# Grove_-_Gas_Sensor_O2_v1_0.net
KiCad netlist of a schematic drawn in EAGLE
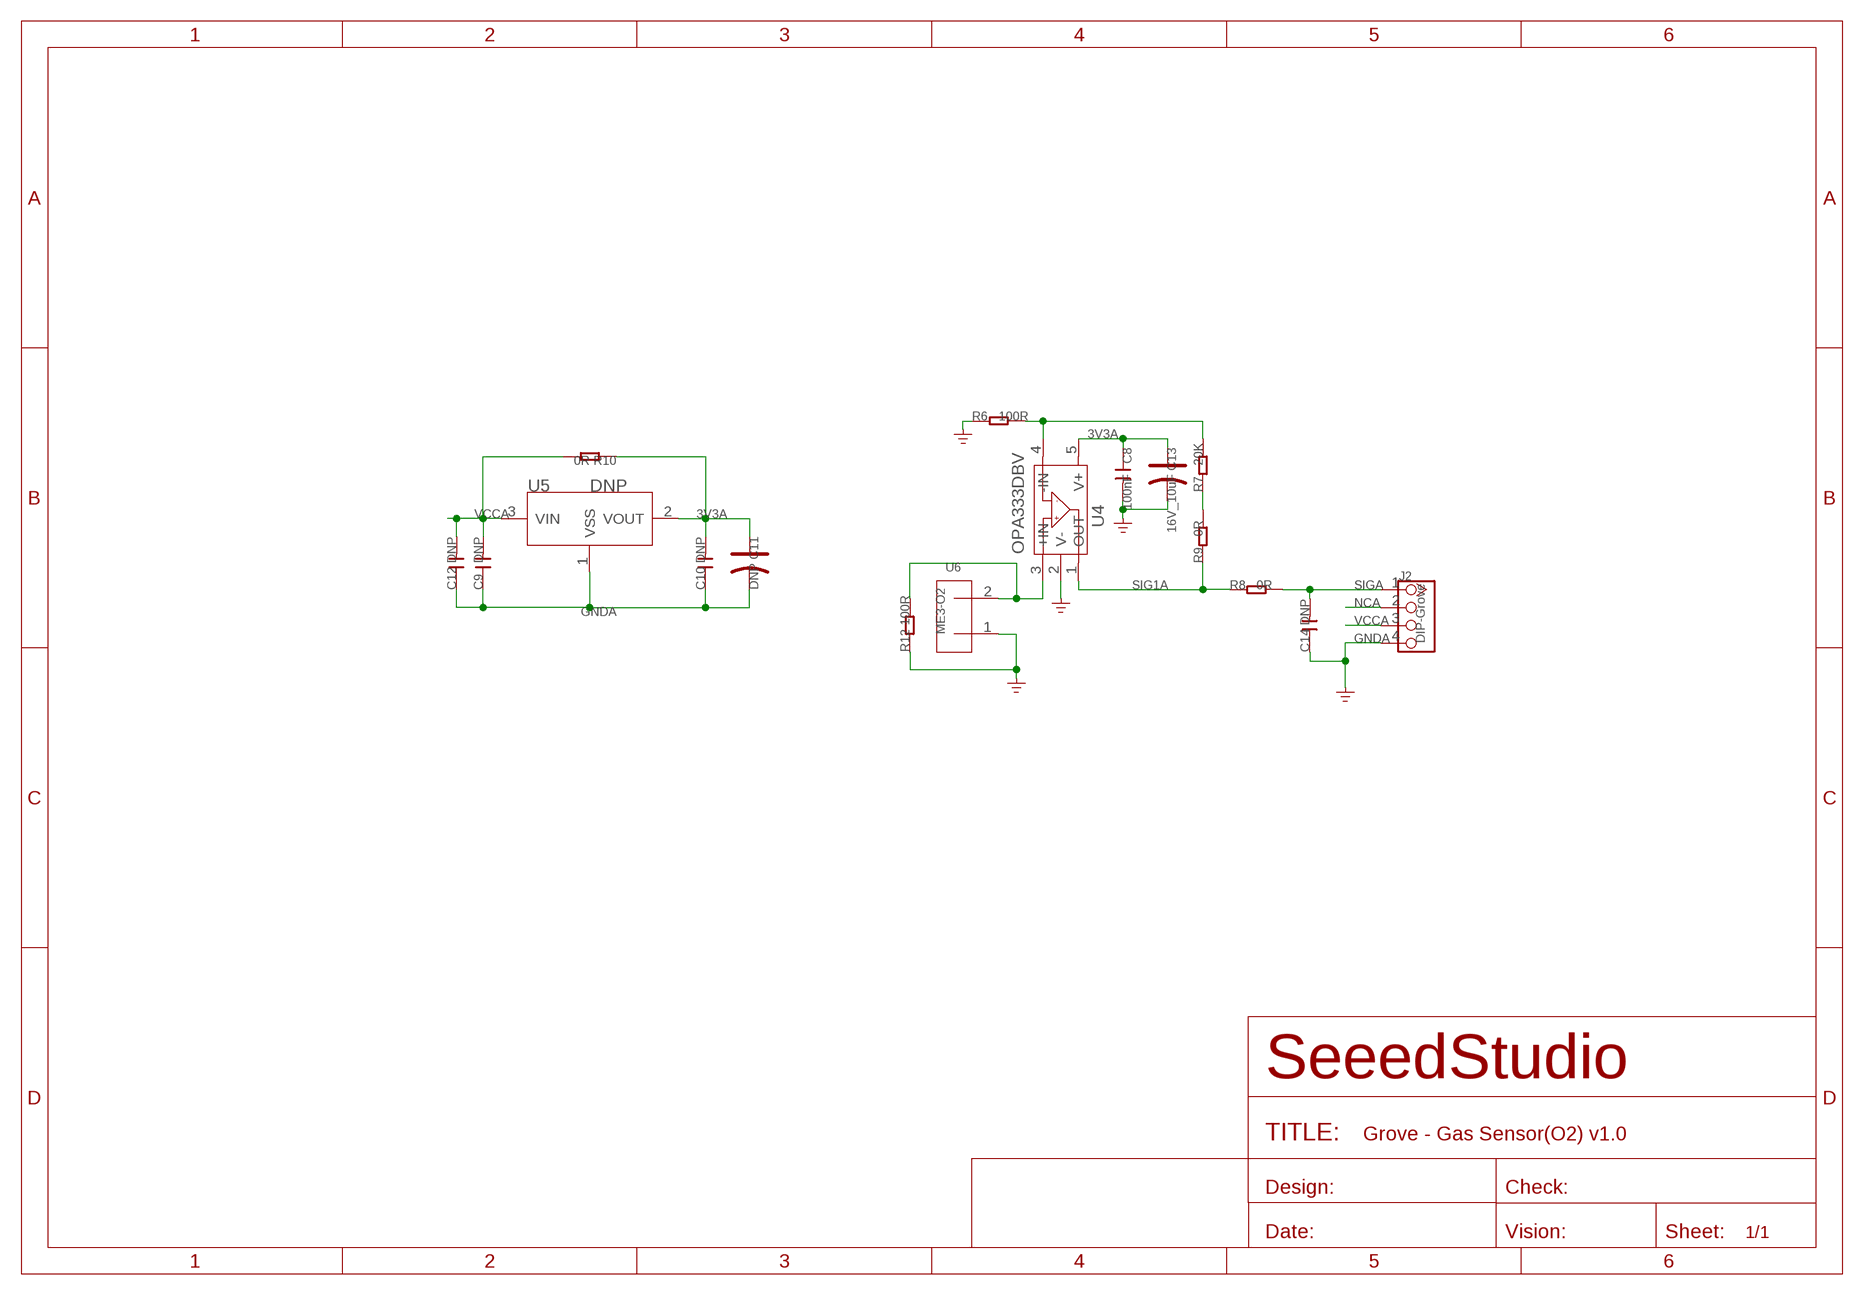
[diagram p0: schematic, sheet 1]

(export (version "E")
  (design (tool "Eeschema 10.0.6"))
  (components
    (comp (ref "C8")
      (value "100nF")
      (footprint "eagle-import:C0603")
      (libsource (lib "eagle-import") (part "C-0603"))
    )
    (comp (ref "C9")
      (value "DNP")
      (footprint "eagle-import:C0603")
      (libsource (lib "eagle-import") (part "C-0603"))
    )
    (comp (ref "C10")
      (value "DNP")
      (footprint "eagle-import:C0603")
      (libsource (lib "eagle-import") (part "C-0603"))
    )
    (comp (ref "C11")
      (value "DNP")
      (footprint "eagle-import:AVX-A")
      (libsource (lib "eagle-import") (part "CAP-AVX-A"))
    )
    (comp (ref "C12")
      (value "DNP")
      (footprint "eagle-import:C0805")
      (libsource (lib "eagle-import") (part "C-0805"))
    )
    (comp (ref "C13")
      (value "16V_10uF")
      (footprint "eagle-import:AVX-A")
      (libsource (lib "eagle-import") (part "CAP-AVX-A"))
    )
    (comp (ref "C14")
      (value "DNP")
      (footprint "eagle-import:C0805")
      (libsource (lib "eagle-import") (part "C-0805"))
    )
    (comp (ref "J2")
      (value "DIP-Grove")
      (footprint "eagle-import:4P-2.0")
      (libsource (lib "eagle-import") (part "TWIG-4P-2.0-2.0"))
    )
    (comp (ref "R6")
      (value "100R")
      (footprint "eagle-import:R0603")
      (libsource (lib "eagle-import") (part "R-0603"))
    )
    (comp (ref "R7")
      (value "20K")
      (footprint "eagle-import:R0603")
      (libsource (lib "eagle-import") (part "R-0603"))
    )
    (comp (ref "R8")
      (value "0R")
      (footprint "eagle-import:R0603")
      (libsource (lib "eagle-import") (part "R-0603"))
    )
    (comp (ref "R9")
      (value "0R")
      (footprint "eagle-import:R0603")
      (libsource (lib "eagle-import") (part "R-0603"))
    )
    (comp (ref "R10")
      (value "0R")
      (footprint "eagle-import:R0603")
      (libsource (lib "eagle-import") (part "R-0603"))
    )
    (comp (ref "R12")
      (value "100R")
      (footprint "eagle-import:R0603")
      (libsource (lib "eagle-import") (part "R-0603"))
    )
    (comp (ref "U4")
      (value "OPA333DBV")
      (footprint "eagle-import:SOT23-5")
      (libsource (lib "eagle-import") (part "OPA333DBV"))
    )
    (comp (ref "U5")
      (value "DNP")
      (footprint "eagle-import:SOT23")
      (libsource (lib "eagle-import") (part "XC6206MR"))
    )
    (comp (ref "U6")
      (value "ME3-O2")
      (footprint "eagle-import:2P-D20X16H")
      (libsource (lib "eagle-import") (part "ME3-O2"))
    )
  )
  (nets
    (net (code "1") (name "/3V3A") (class "Default")
      (node (ref "C10") (pin "2") (pinfunction "2_2") (pintype "passive"))
      (node (ref "C11") (pin "+") (pinfunction "+_+") (pintype "passive"))
      (node (ref "C13") (pin "+") (pinfunction "+_+") (pintype "passive"))
      (node (ref "C8") (pin "1") (pinfunction "1_1") (pintype "passive"))
      (node (ref "R10") (pin "1") (pinfunction "1_1") (pintype "passive"))
      (node (ref "U4") (pin "5") (pinfunction "V+_5") (pintype "bidirectional"))
      (node (ref "U5") (pin "2") (pinfunction "VOUT_2") (pintype "output"))
    )
    (net (code "2") (name "/NCA") (class "Default")
      (node (ref "J2") (pin "2") (pinfunction "2_2") (pintype "bidirectional"))
    )
    (net (code "3") (name "/SIG1A") (class "Default")
      (node (ref "R8") (pin "1") (pinfunction "1_1") (pintype "passive"))
      (node (ref "R9") (pin "1") (pinfunction "1_1") (pintype "passive"))
      (node (ref "U4") (pin "1") (pinfunction "OUT_1") (pintype "bidirectional"))
    )
    (net (code "4") (name "/SIGA") (class "Default")
      (node (ref "C14") (pin "2") (pinfunction "2_2") (pintype "passive"))
      (node (ref "J2") (pin "1") (pinfunction "1_1") (pintype "bidirectional"))
      (node (ref "R8") (pin "2") (pinfunction "2_2") (pintype "passive"))
    )
    (net (code "5") (name "/VCCA") (class "Default")
      (node (ref "C12") (pin "2") (pinfunction "2_2") (pintype "passive"))
      (node (ref "C9") (pin "2") (pinfunction "2_2") (pintype "passive"))
      (node (ref "J2") (pin "3") (pinfunction "3_3") (pintype "bidirectional"))
      (node (ref "R10") (pin "2") (pinfunction "2_2") (pintype "passive"))
      (node (ref "U5") (pin "3") (pinfunction "VIN_3") (pintype "input"))
    )
    (net (code "6") (name "GND_POWER") (class "Default")
      (node (ref "C10") (pin "1") (pinfunction "1_1") (pintype "passive"))
      (node (ref "C11") (pin "-") (pinfunction "-_-") (pintype "passive"))
      (node (ref "C12") (pin "1") (pinfunction "1_1") (pintype "passive"))
      (node (ref "C13") (pin "-") (pinfunction "-_-") (pintype "passive"))
      (node (ref "C14") (pin "1") (pinfunction "1_1") (pintype "passive"))
      (node (ref "C8") (pin "2") (pinfunction "2_2") (pintype "passive"))
      (node (ref "C9") (pin "1") (pinfunction "1_1") (pintype "passive"))
      (node (ref "J2") (pin "4") (pinfunction "4_4") (pintype "bidirectional"))
      (node (ref "R12") (pin "1") (pinfunction "1_1") (pintype "passive"))
      (node (ref "R6") (pin "1") (pinfunction "1_1") (pintype "passive"))
      (node (ref "U4") (pin "2") (pinfunction "V-_2") (pintype "bidirectional"))
      (node (ref "U5") (pin "1") (pinfunction "VSS_1") (pintype "power_in"))
      (node (ref "U6") (pin "1") (pinfunction "1_1") (pintype "bidirectional"))
    )
    (net (code "7") (name "Net-(R7-Pad1)") (class "Default")
      (node (ref "R7") (pin "1") (pinfunction "1_1") (pintype "passive"))
      (node (ref "R9") (pin "2") (pinfunction "2_2") (pintype "passive"))
    )
    (net (code "8") (name "Net-(U4-+IN)") (class "Default")
      (node (ref "R12") (pin "2") (pinfunction "2_2") (pintype "passive"))
      (node (ref "U4") (pin "3") (pinfunction "+IN_3") (pintype "bidirectional"))
      (node (ref "U6") (pin "2") (pinfunction "2_2") (pintype "bidirectional"))
    )
    (net (code "9") (name "Net-(U4--IN)") (class "Default")
      (node (ref "R6") (pin "2") (pinfunction "2_2") (pintype "passive"))
      (node (ref "R7") (pin "2") (pinfunction "2_2") (pintype "passive"))
      (node (ref "U4") (pin "4") (pinfunction "-IN_4") (pintype "bidirectional"))
    )
  )
)
